# USB.net
KiCad netlist of a schematic drawn in Altium Designer
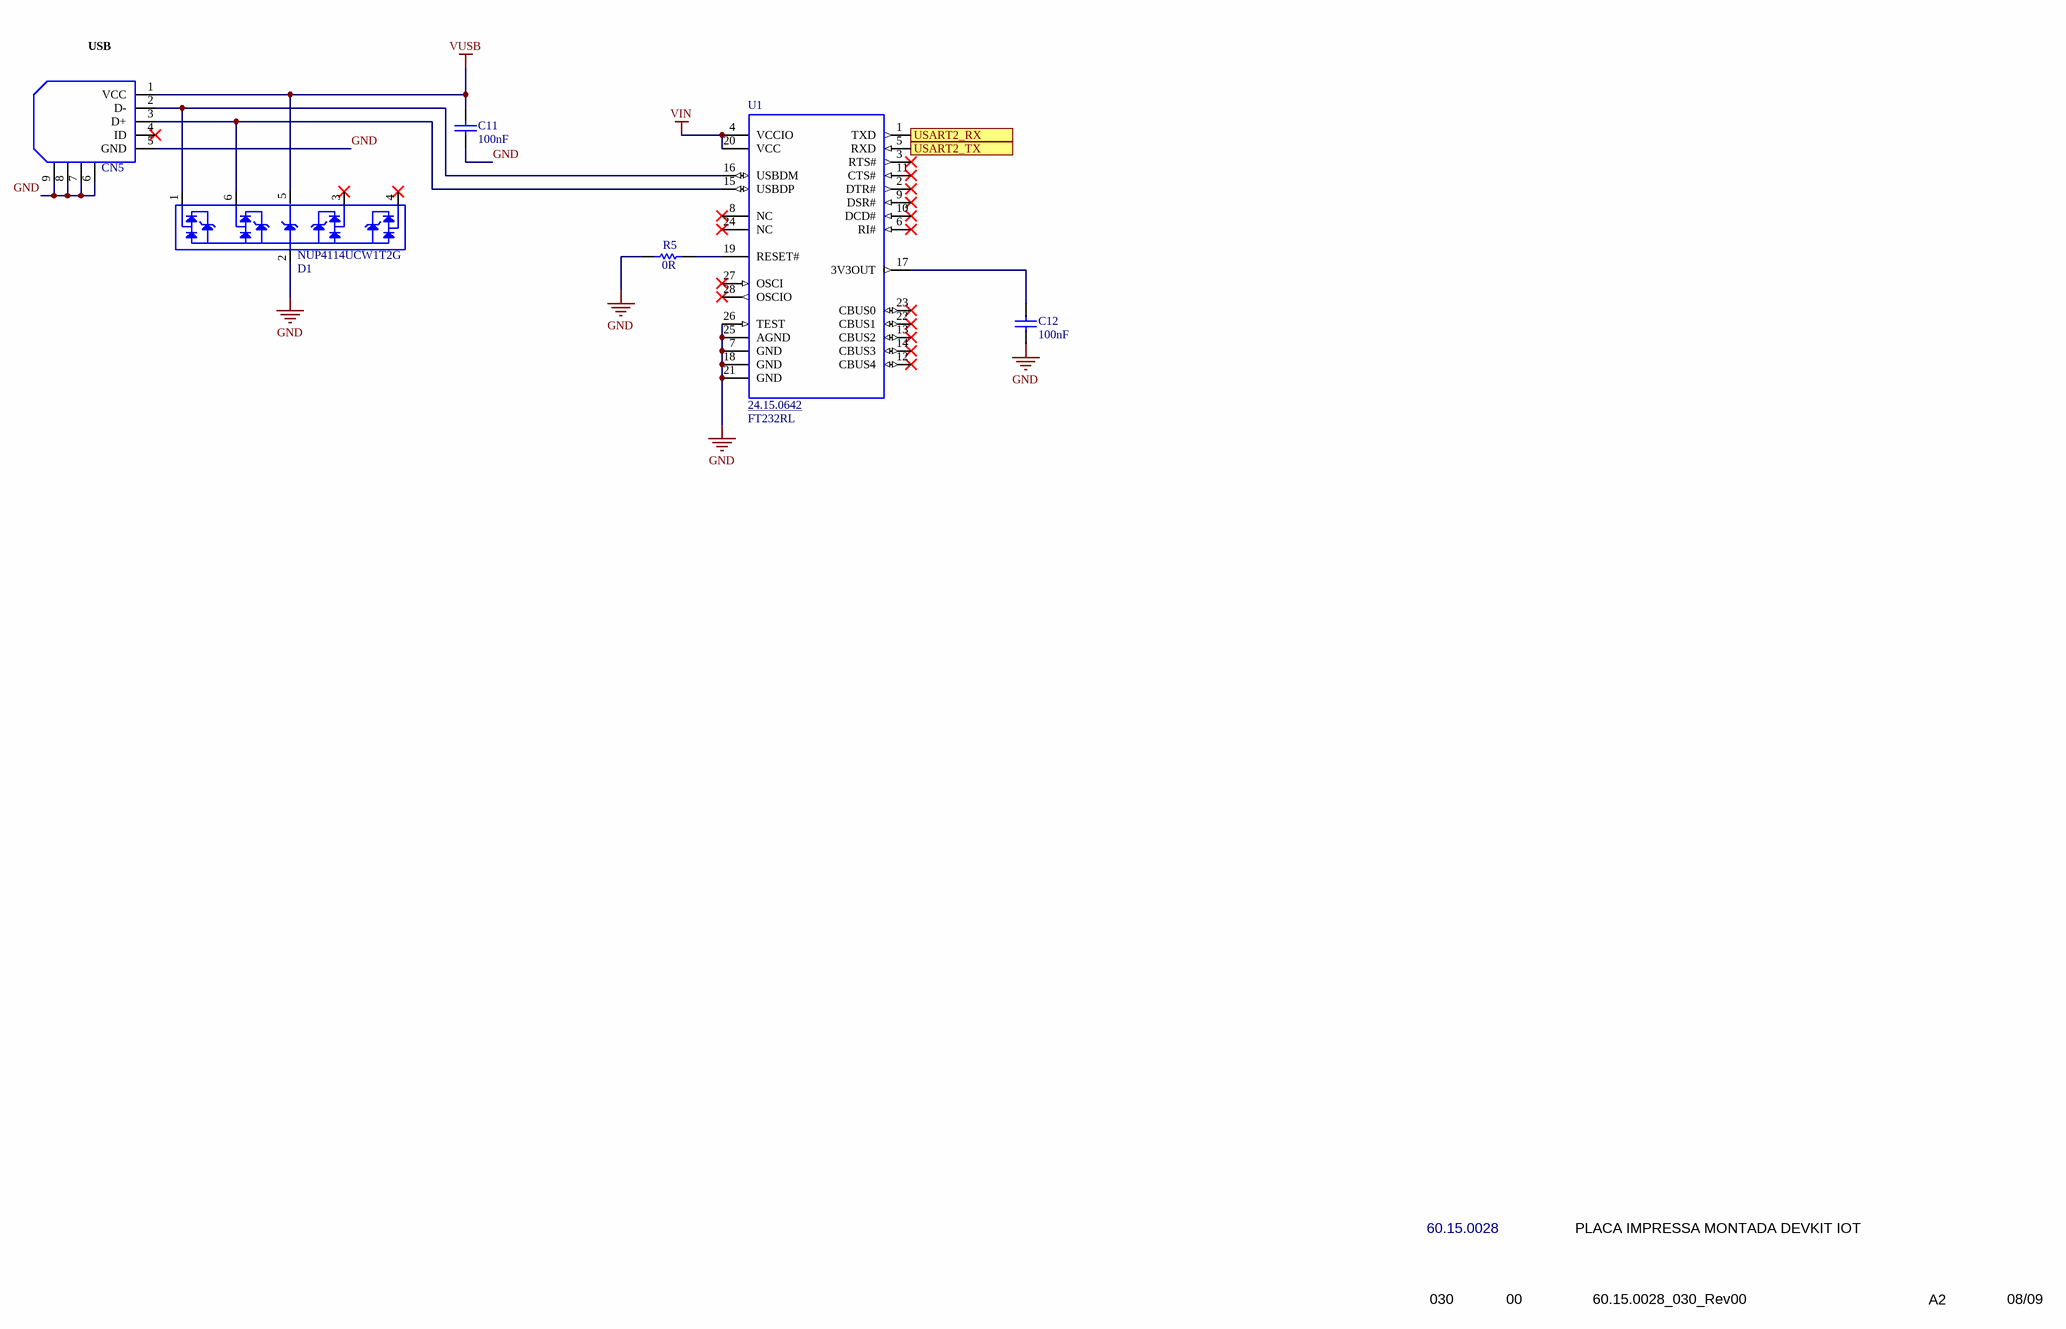
[diagram p0: USB.SchDoc]

(export (version "E")
  (design (tool "Eeschema 10.0.6"))
  (components
    (comp (ref "C11")
      (value "16.23.0803")
      (footprint "16.23.0803")
      (description "CAPACITOR CERAMICO 100nF 16V 10%% X5R SMD 0201")
      (fields (field (name "ALTIUM_UNNAMED_1") "100nF"))
      (libsource (lib "OMNI-CAPACITORES") (part "16.23.0803"))
    )
    (comp (ref "C12")
      (value "100nF")
      (footprint "16.23.0023")
      (description "CC SMD 100NF 50V X7R 10% 0805")
      (fields (field (name "Comment") "16.23.0023"))
      (libsource (lib "OMNI-CAPACITORES") (part "16.23.0023"))
    )
    (comp (ref "CN5")
      (value "28.14.0512")
      (footprint "28.14.0512")
      (description "CONN USB MICRO B RECPT SMT R/A")
      (libsource (lib "OMNI-CONECTORES") (part "28.14.0512"))
    )
    (comp (ref "D1")
      (value "32.27.0043")
      (footprint "32.27.0043")
      (description "DIODO SUPRESSOR 5.5V 10V SC88")
      (fields (field (name "ALTIUM_UNNAMED_1") "NUP4114UCW1T2G"))
      (libsource (lib "OMNI-DIODOS_LED´s_DISPLAYS") (part "32.27.0043"))
    )
    (comp (ref "R5")
      (value "0R")
      (footprint "66.24.1337")
      (description "RESISTOR THICK FILM 0,1W 0 OHMS SMD 0603")
      (fields (field (name "Comment") "66.24.1337"))
      (libsource (lib "OMNI-RESISTORES") (part "66.24.1337"))
    )
    (comp (ref "U1")
      (value "24.15.0642")
      (footprint "24.15.0642")
      (description "CID CONVERSOR USB PARA SERIAL SSOP-28")
      (fields (field (name "PART NUMBER") "FT232RL"))
      (libsource (lib "OMNI-CI´S DIGITAIS") (part "24.15.0642"))
    )
  )
  (nets
    (net (code "1") (name "/USART2_RX") (class "Default")
      (node (ref "U1") (pin "1") (pinfunction "TXD_1") (pintype "output"))
    )
    (net (code "2") (name "/USART2_TX") (class "Default")
      (node (ref "U1") (pin "5") (pinfunction "RXD_5") (pintype "input"))
    )
    (net (code "3") (name "GND") (class "Default")
      (node (ref "C11") (pin "1") (pinfunction "1_1") (pintype "passive"))
      (node (ref "C12") (pin "1") (pinfunction "1_1") (pintype "passive"))
      (node (ref "CN5") (pin "5") (pinfunction "GND_5") (pintype "passive"))
      (node (ref "CN5") (pin "6") (pinfunction "SHIELD_6") (pintype "passive"))
      (node (ref "CN5") (pin "7") (pinfunction "SHIELD_7") (pintype "passive"))
      (node (ref "CN5") (pin "8") (pinfunction "SHIELD_8") (pintype "passive"))
      (node (ref "CN5") (pin "9") (pinfunction "SHIELD_9") (pintype "passive"))
      (node (ref "D1") (pin "2") (pinfunction "2_2") (pintype "power_in"))
      (node (ref "R5") (pin "1") (pinfunction "1_1") (pintype "passive"))
      (node (ref "U1") (pin "18") (pinfunction "GND_18") (pintype "power_in"))
      (node (ref "U1") (pin "21") (pinfunction "GND_21") (pintype "power_in"))
      (node (ref "U1") (pin "25") (pinfunction "AGND_25") (pintype "power_in"))
      (node (ref "U1") (pin "26") (pinfunction "TEST_26") (pintype "input"))
      (node (ref "U1") (pin "7") (pinfunction "GND_7") (pintype "power_in"))
    )
    (net (code "4") (name "Net-(CN5-D+)") (class "Default")
      (node (ref "CN5") (pin "3") (pinfunction "D+_3") (pintype "passive"))
      (node (ref "D1") (pin "6") (pinfunction "6_6") (pintype "passive"))
      (node (ref "U1") (pin "15") (pinfunction "USBDP_15") (pintype "bidirectional"))
    )
    (net (code "5") (name "Net-(CN5-D-)") (class "Default")
      (node (ref "CN5") (pin "2") (pinfunction "D-_2") (pintype "passive"))
      (node (ref "D1") (pin "1") (pinfunction "1_1") (pintype "passive"))
      (node (ref "U1") (pin "16") (pinfunction "USBDM_16") (pintype "bidirectional"))
    )
    (net (code "6") (name "Net-(U1-3V3OUT)") (class "Default")
      (node (ref "C12") (pin "2") (pinfunction "2_2") (pintype "passive"))
      (node (ref "U1") (pin "17") (pinfunction "3V3OUT_17") (pintype "output"))
    )
    (net (code "7") (name "Net-(U1-RESET#)") (class "Default")
      (node (ref "R5") (pin "2") (pinfunction "2_2") (pintype "passive"))
      (node (ref "U1") (pin "19") (pinfunction "RESET#_19") (pintype "power_in"))
    )
    (net (code "8") (name "VIN") (class "Default")
      (node (ref "U1") (pin "20") (pinfunction "VCC_20") (pintype "power_in"))
      (node (ref "U1") (pin "4") (pinfunction "VCCIO_4") (pintype "power_in"))
    )
    (net (code "9") (name "VUSB") (class "Default")
      (node (ref "C11") (pin "2") (pinfunction "2_2") (pintype "passive"))
      (node (ref "CN5") (pin "1") (pinfunction "VCC_1") (pintype "passive"))
      (node (ref "D1") (pin "5") (pinfunction "5_5") (pintype "power_in"))
    )
    (net (code "10") (name "unconnected-(CN5-ID-Pad4)") (class "Default")
      (node (ref "CN5") (pin "4") (pinfunction "ID_4") (pintype "passive+no_connect"))
    )
    (net (code "11") (name "unconnected-(D1-Pad3)") (class "Default")
      (node (ref "D1") (pin "3") (pinfunction "3_3") (pintype "passive+no_connect"))
    )
    (net (code "12") (name "unconnected-(D1-Pad4)") (class "Default")
      (node (ref "D1") (pin "4") (pinfunction "4_4") (pintype "passive+no_connect"))
    )
    (net (code "13") (name "unconnected-(U1-CBUS0-Pad23)") (class "Default")
      (node (ref "U1") (pin "23") (pinfunction "CBUS0_23") (pintype "bidirectional+no_connect"))
    )
    (net (code "14") (name "unconnected-(U1-CBUS1-Pad22)") (class "Default")
      (node (ref "U1") (pin "22") (pinfunction "CBUS1_22") (pintype "bidirectional+no_connect"))
    )
    (net (code "15") (name "unconnected-(U1-CBUS2-Pad13)") (class "Default")
      (node (ref "U1") (pin "13") (pinfunction "CBUS2_13") (pintype "bidirectional+no_connect"))
    )
    (net (code "16") (name "unconnected-(U1-CBUS3-Pad14)") (class "Default")
      (node (ref "U1") (pin "14") (pinfunction "CBUS3_14") (pintype "bidirectional+no_connect"))
    )
    (net (code "17") (name "unconnected-(U1-CBUS4-Pad12)") (class "Default")
      (node (ref "U1") (pin "12") (pinfunction "CBUS4_12") (pintype "bidirectional+no_connect"))
    )
    (net (code "18") (name "unconnected-(U1-CTS#-Pad11)") (class "Default")
      (node (ref "U1") (pin "11") (pinfunction "CTS#_11") (pintype "input+no_connect"))
    )
    (net (code "19") (name "unconnected-(U1-DCD#-Pad10)") (class "Default")
      (node (ref "U1") (pin "10") (pinfunction "DCD#_10") (pintype "input+no_connect"))
    )
    (net (code "20") (name "unconnected-(U1-DSR#-Pad9)") (class "Default")
      (node (ref "U1") (pin "9") (pinfunction "DSR#_9") (pintype "input+no_connect"))
    )
    (net (code "21") (name "unconnected-(U1-DTR#-Pad2)") (class "Default")
      (node (ref "U1") (pin "2") (pinfunction "DTR#_2") (pintype "output+no_connect"))
    )
    (net (code "22") (name "unconnected-(U1-NC-Pad8)") (class "Default")
      (node (ref "U1") (pin "8") (pinfunction "NC_8") (pintype "passive+no_connect"))
    )
    (net (code "23") (name "unconnected-(U1-NC-Pad24)") (class "Default")
      (node (ref "U1") (pin "24") (pinfunction "NC_24") (pintype "passive+no_connect"))
    )
    (net (code "24") (name "unconnected-(U1-OSCI-Pad27)") (class "Default")
      (node (ref "U1") (pin "27") (pinfunction "OSCI_27") (pintype "input+no_connect"))
    )
    (net (code "25") (name "unconnected-(U1-OSCIO-Pad28)") (class "Default")
      (node (ref "U1") (pin "28") (pinfunction "OSCIO_28") (pintype "output+no_connect"))
    )
    (net (code "26") (name "unconnected-(U1-RI#-Pad6)") (class "Default")
      (node (ref "U1") (pin "6") (pinfunction "RI#_6") (pintype "input+no_connect"))
    )
    (net (code "27") (name "unconnected-(U1-RTS#-Pad3)") (class "Default")
      (node (ref "U1") (pin "3") (pinfunction "RTS#_3") (pintype "output+no_connect"))
    )
  )
)
